# Terminal.net
KiCad netlist of a schematic drawn in Altium Designer
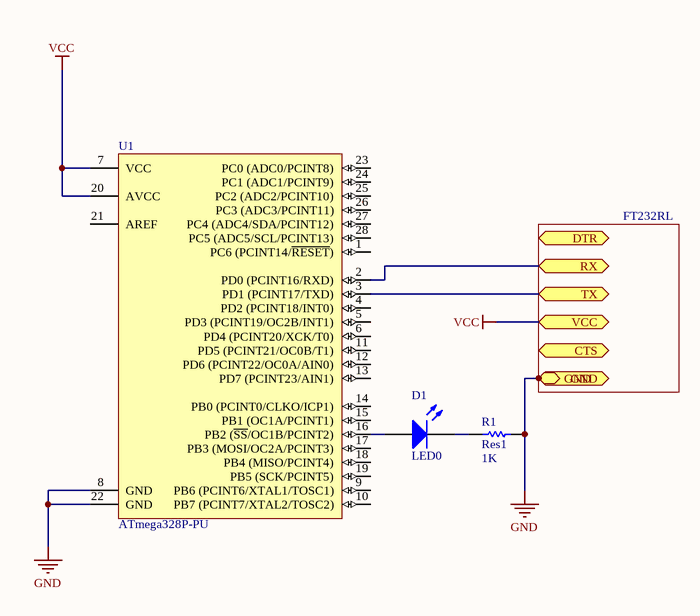
[diagram p0: Terminal.SchDoc]

(export (version "E")
  (design (tool "Eeschema 10.0.6"))
  (components
    (comp (ref "D1")
      (value "LED0")
      (footprint "LED-0")
      (description "Typical INFRARED GaAs LED")
      (fields (field (name "PUBLISHER") "Altium Limited"))
      (libsource (lib "Miscellaneous Devices") (part "LED0"))
    )
    (comp (ref "R1")
      (value "Res1")
      (footprint "AXIAL-0.3")
      (description "Resistor")
      (fields (field (name "ALTIUM_VALUE") "1K") (field (name "PUBLISHER") "Altium Limited"))
      (libsource (lib "Miscellaneous Devices") (part "Res1"))
    )
    (comp (ref "U1")
      (value "ATmega328P-PU")
      (footprint "28P3")
      (fields (field (name "PUBLISHER") "Altium Limited"))
      (libsource (lib "Atmel Microcontroller 8-Bit megaAVR") (part "ATmega328P-PU"))
    )
  )
  (nets
    (net (code "3") (name "/RX") (class "Default")
      (node (ref "U1") (pin "2") (pinfunction "PD0_(PCINT16/RXD)_2") (pintype "bidirectional"))
    )
    (net (code "4") (name "/TX") (class "Default")
      (node (ref "U1") (pin "3") (pinfunction "PD1_(PCINT17/TXD)_3") (pintype "bidirectional"))
    )
    (net (code "5") (name "GND") (class "Default")
      (node (ref "R1") (pin "2") (pinfunction "2_2") (pintype "passive"))
      (node (ref "U1") (pin "22") (pinfunction "GND_22") (pintype "power_in"))
      (node (ref "U1") (pin "8") (pinfunction "GND_8") (pintype "power_in"))
    )
    (net (code "6") (name "Net-(D1-A)") (class "Default")
      (node (ref "D1") (pin "1") (pinfunction "A_1") (pintype "passive"))
      (node (ref "U1") (pin "16") (pinfunction "PB2_(~{SS}/OC1B/PCINT2)_16") (pintype "bidirectional"))
    )
    (net (code "7") (name "Net-(D1-K)") (class "Default")
      (node (ref "D1") (pin "2") (pinfunction "K_2") (pintype "passive"))
      (node (ref "R1") (pin "1") (pinfunction "1_1") (pintype "passive"))
    )
    (net (code "8") (name "VCC") (class "Default")
      (node (ref "U1") (pin "20") (pinfunction "AVCC_20") (pintype "power_in"))
      (node (ref "U1") (pin "7") (pinfunction "VCC_7") (pintype "power_in"))
    )
    (net (code "9") (name "unconnected-(U1-AREF-Pad21)") (class "Default")
      (node (ref "U1") (pin "21") (pinfunction "AREF_21") (pintype "power_in"))
    )
    (net (code "10") (name "unconnected-(U1-PB0_(PCINT0{slash}CLKO{slash}ICP1)-Pad14)") (class "Default")
      (node (ref "U1") (pin "14") (pinfunction "PB0_(PCINT0/CLKO/ICP1)_14") (pintype "bidirectional"))
    )
    (net (code "11") (name "unconnected-(U1-PB1_(OC1A{slash}PCINT1)-Pad15)") (class "Default")
      (node (ref "U1") (pin "15") (pinfunction "PB1_(OC1A/PCINT1)_15") (pintype "bidirectional"))
    )
    (net (code "12") (name "unconnected-(U1-PB3_(MOSI{slash}OC2A{slash}PCINT3)-Pad17)") (class "Default")
      (node (ref "U1") (pin "17") (pinfunction "PB3_(MOSI/OC2A/PCINT3)_17") (pintype "bidirectional"))
    )
    (net (code "13") (name "unconnected-(U1-PB4_(MISO{slash}PCINT4)-Pad18)") (class "Default")
      (node (ref "U1") (pin "18") (pinfunction "PB4_(MISO/PCINT4)_18") (pintype "bidirectional"))
    )
    (net (code "14") (name "unconnected-(U1-PB5_(SCK{slash}PCINT5)-Pad19)") (class "Default")
      (node (ref "U1") (pin "19") (pinfunction "PB5_(SCK/PCINT5)_19") (pintype "bidirectional"))
    )
    (net (code "15") (name "unconnected-(U1-PB6_(PCINT6{slash}XTAL1{slash}TOSC1)-Pad9)") (class "Default")
      (node (ref "U1") (pin "9") (pinfunction "PB6_(PCINT6/XTAL1/TOSC1)_9") (pintype "bidirectional"))
    )
    (net (code "16") (name "unconnected-(U1-PB7_(PCINT7{slash}XTAL2{slash}TOSC2)-Pad10)") (class "Default")
      (node (ref "U1") (pin "10") (pinfunction "PB7_(PCINT7/XTAL2/TOSC2)_10") (pintype "bidirectional"))
    )
    (net (code "17") (name "unconnected-(U1-PC0_(ADC0{slash}PCINT8)-Pad23)") (class "Default")
      (node (ref "U1") (pin "23") (pinfunction "PC0_(ADC0/PCINT8)_23") (pintype "bidirectional"))
    )
    (net (code "18") (name "unconnected-(U1-PC1_(ADC1{slash}PCINT9)-Pad24)") (class "Default")
      (node (ref "U1") (pin "24") (pinfunction "PC1_(ADC1/PCINT9)_24") (pintype "bidirectional"))
    )
    (net (code "19") (name "unconnected-(U1-PC2_(ADC2{slash}PCINT10)-Pad25)") (class "Default")
      (node (ref "U1") (pin "25") (pinfunction "PC2_(ADC2/PCINT10)_25") (pintype "bidirectional"))
    )
    (net (code "20") (name "unconnected-(U1-PC3_(ADC3{slash}PCINT11)-Pad26)") (class "Default")
      (node (ref "U1") (pin "26") (pinfunction "PC3_(ADC3/PCINT11)_26") (pintype "bidirectional"))
    )
    (net (code "21") (name "unconnected-(U1-PC4_(ADC4{slash}SDA{slash}PCINT12)-Pad27)") (class "Default")
      (node (ref "U1") (pin "27") (pinfunction "PC4_(ADC4/SDA/PCINT12)_27") (pintype "bidirectional"))
    )
    (net (code "22") (name "unconnected-(U1-PC5_(ADC5{slash}SCL{slash}PCINT13)-Pad28)") (class "Default")
      (node (ref "U1") (pin "28") (pinfunction "PC5_(ADC5/SCL/PCINT13)_28") (pintype "bidirectional"))
    )
    (net (code "23") (name "unconnected-(U1-PC6_(PCINT14{slash}~{RESET})-Pad1)") (class "Default")
      (node (ref "U1") (pin "1") (pinfunction "PC6_(PCINT14/~{RESET})_1") (pintype "bidirectional"))
    )
    (net (code "24") (name "unconnected-(U1-PD2_(PCINT18{slash}INT0)-Pad4)") (class "Default")
      (node (ref "U1") (pin "4") (pinfunction "PD2_(PCINT18/INT0)_4") (pintype "bidirectional"))
    )
    (net (code "25") (name "unconnected-(U1-PD3_(PCINT19{slash}OC2B{slash}INT1)-Pad5)") (class "Default")
      (node (ref "U1") (pin "5") (pinfunction "PD3_(PCINT19/OC2B/INT1)_5") (pintype "bidirectional"))
    )
    (net (code "26") (name "unconnected-(U1-PD4_(PCINT20{slash}XCK{slash}T0)-Pad6)") (class "Default")
      (node (ref "U1") (pin "6") (pinfunction "PD4_(PCINT20/XCK/T0)_6") (pintype "bidirectional"))
    )
    (net (code "27") (name "unconnected-(U1-PD5_(PCINT21{slash}OC0B{slash}T1)-Pad11)") (class "Default")
      (node (ref "U1") (pin "11") (pinfunction "PD5_(PCINT21/OC0B/T1)_11") (pintype "bidirectional"))
    )
    (net (code "28") (name "unconnected-(U1-PD6_(PCINT22{slash}OC0A{slash}AIN0)-Pad12)") (class "Default")
      (node (ref "U1") (pin "12") (pinfunction "PD6_(PCINT22/OC0A/AIN0)_12") (pintype "bidirectional"))
    )
    (net (code "29") (name "unconnected-(U1-PD7_(PCINT23{slash}AIN1)-Pad13)") (class "Default")
      (node (ref "U1") (pin "13") (pinfunction "PD7_(PCINT23/AIN1)_13") (pintype "bidirectional"))
    )
  )
)
